# main.net
KiCad netlist of a schematic drawn in EAGLE
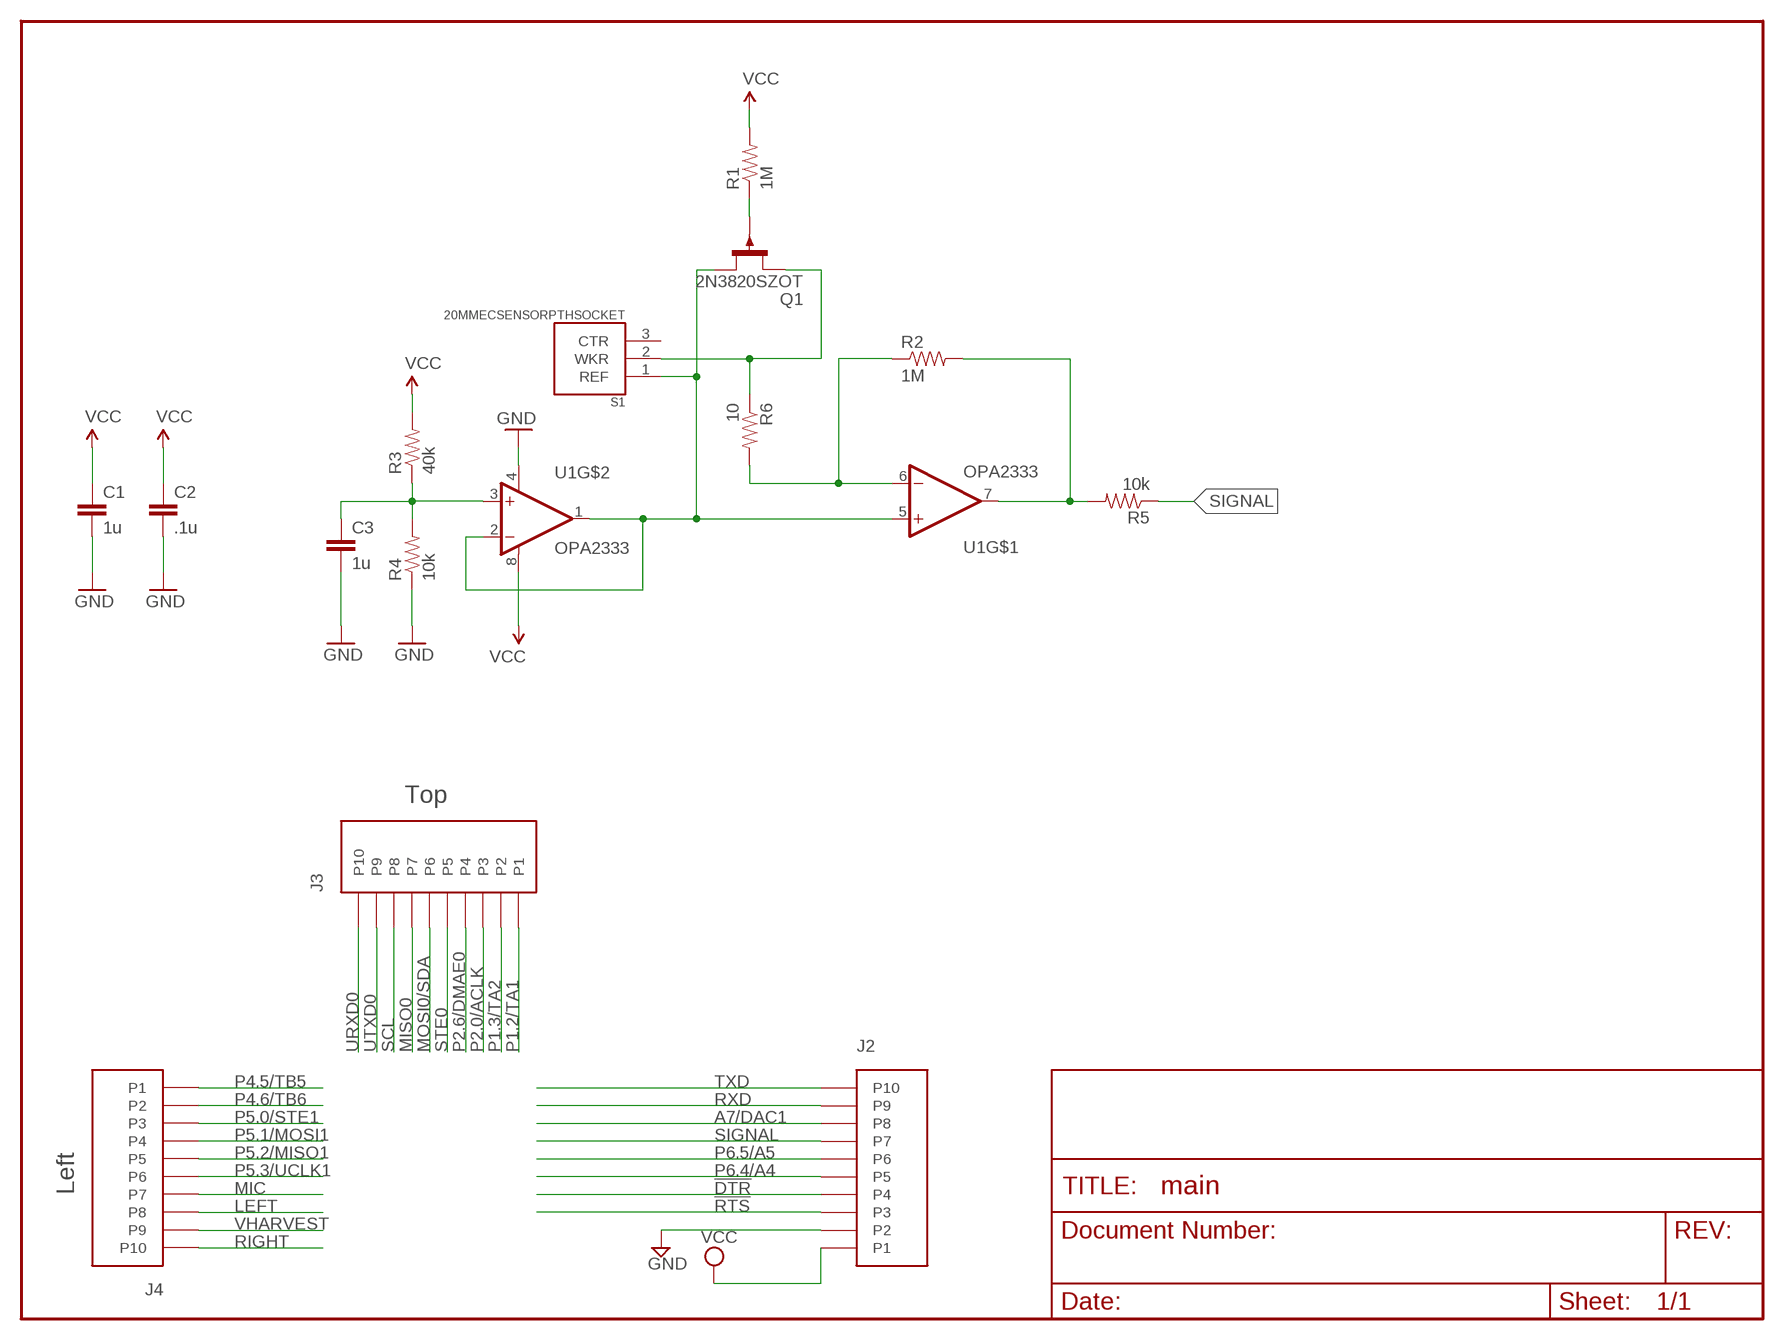
[diagram p0: schematic, sheet 1]

(export (version "E")
  (design (tool "Eeschema 10.0.6"))
  (components
    (comp (ref "C1")
      (value "1u")
      (footprint "eagle-import:0603-CAP")
      (libsource (lib "eagle-import") (part "CAP0603-CAP"))
    )
    (comp (ref "C2")
      (value ".1u")
      (footprint "eagle-import:0603-CAP")
      (libsource (lib "eagle-import") (part "CAP0603-CAP"))
    )
    (comp (ref "C3")
      (value "1u")
      (footprint "eagle-import:0603-CAP")
      (libsource (lib "eagle-import") (part "CAP0603-CAP"))
    )
    (comp (ref "J2")
      (value "HEADER10POS")
      (footprint "eagle-import:10PIN2MMHEADER")
      (libsource (lib "eagle-import") (part "HEADER10POS"))
    )
    (comp (ref "J3")
      (value "HEADER10POS")
      (footprint "eagle-import:10PIN2MMHEADER")
      (libsource (lib "eagle-import") (part "HEADER10POS"))
    )
    (comp (ref "J4")
      (value "HEADER10POS")
      (footprint "eagle-import:10PIN2MMHEADER")
      (libsource (lib "eagle-import") (part "HEADER10POS"))
    )
    (comp (ref "Q1")
      (value "2N3820SZOT")
      (footprint "eagle-import:SOT23-3")
      (libsource (lib "eagle-import") (part "2N3820SZOT"))
    )
    (comp (ref "R1")
      (value "1M")
      (footprint "eagle-import:0603-RES")
      (libsource (lib "eagle-import") (part "RESISTOR0603-RES"))
    )
    (comp (ref "R2")
      (value "1M")
      (footprint "eagle-import:0603-RES")
      (libsource (lib "eagle-import") (part "RESISTOR0603-RES"))
    )
    (comp (ref "R3")
      (value "40k")
      (footprint "eagle-import:0603-RES")
      (libsource (lib "eagle-import") (part "RESISTOR0603-RES"))
    )
    (comp (ref "R4")
      (value "10k")
      (footprint "eagle-import:0603-RES")
      (libsource (lib "eagle-import") (part "RESISTOR0603-RES"))
    )
    (comp (ref "R5")
      (value "10k")
      (footprint "eagle-import:0603-RES")
      (libsource (lib "eagle-import") (part "RESISTOR0603-RES"))
    )
    (comp (ref "R6")
      (value "10")
      (footprint "eagle-import:0603-RES")
      (libsource (lib "eagle-import") (part "RESISTOR0603-RES"))
    )
    (comp (ref "S1")
      (value "20MMECSENSORPTHSOCKET")
      (footprint "eagle-import:20MMSENSOR")
      (libsource (lib "eagle-import") (part "20MMECSENSORPTHSOCKET"))
    )
    (comp (ref "U1")
      (value "OPA2333")
      (footprint "eagle-import:SOIC")
      (libsource (lib "eagle-import") (part "OPA2333"))
    )
  )
  (nets
    (net (code "1") (name "/A7{slash}DAC1") (class "Default")
      (node (ref "J2") (pin "P8") (pinfunction "P8_P8") (pintype "bidirectional"))
    )
    (net (code "2") (name "/LEFT") (class "Default")
      (node (ref "J4") (pin "P8") (pinfunction "P8_P8") (pintype "bidirectional"))
    )
    (net (code "3") (name "/MIC") (class "Default")
      (node (ref "J4") (pin "P7") (pinfunction "P7_P7") (pintype "bidirectional"))
    )
    (net (code "4") (name "/MISO0") (class "Default")
      (node (ref "J3") (pin "P7") (pinfunction "P7_P7") (pintype "bidirectional"))
    )
    (net (code "5") (name "/MOSI0{slash}SDA") (class "Default")
      (node (ref "J3") (pin "P6") (pinfunction "P6_P6") (pintype "bidirectional"))
    )
    (net (code "6") (name "/P1.2{slash}TA1") (class "Default")
      (node (ref "J3") (pin "P1") (pinfunction "P1_P1") (pintype "bidirectional"))
    )
    (net (code "7") (name "/P1.3{slash}TA2") (class "Default")
      (node (ref "J3") (pin "P2") (pinfunction "P2_P2") (pintype "bidirectional"))
    )
    (net (code "8") (name "/P2.0{slash}ACLK") (class "Default")
      (node (ref "J3") (pin "P3") (pinfunction "P3_P3") (pintype "bidirectional"))
    )
    (net (code "9") (name "/P2.6{slash}DMAE0") (class "Default")
      (node (ref "J3") (pin "P4") (pinfunction "P4_P4") (pintype "bidirectional"))
    )
    (net (code "10") (name "/P4.5{slash}TB5") (class "Default")
      (node (ref "J4") (pin "P1") (pinfunction "P1_P1") (pintype "bidirectional"))
    )
    (net (code "11") (name "/P4.6{slash}TB6") (class "Default")
      (node (ref "J4") (pin "P2") (pinfunction "P2_P2") (pintype "bidirectional"))
    )
    (net (code "12") (name "/P5.0{slash}STE1") (class "Default")
      (node (ref "J4") (pin "P3") (pinfunction "P3_P3") (pintype "bidirectional"))
    )
    (net (code "13") (name "/P5.1{slash}MOSI1") (class "Default")
      (node (ref "J4") (pin "P4") (pinfunction "P4_P4") (pintype "bidirectional"))
    )
    (net (code "14") (name "/P5.2{slash}MISO1") (class "Default")
      (node (ref "J4") (pin "P5") (pinfunction "P5_P5") (pintype "bidirectional"))
    )
    (net (code "15") (name "/P5.3{slash}UCLK1") (class "Default")
      (node (ref "J4") (pin "P6") (pinfunction "P6_P6") (pintype "bidirectional"))
    )
    (net (code "16") (name "/P6.4{slash}A4") (class "Default")
      (node (ref "J2") (pin "P5") (pinfunction "P5_P5") (pintype "bidirectional"))
    )
    (net (code "17") (name "/P6.5{slash}A5") (class "Default")
      (node (ref "J2") (pin "P6") (pinfunction "P6_P6") (pintype "bidirectional"))
    )
    (net (code "18") (name "/RIGHT") (class "Default")
      (node (ref "J4") (pin "P10") (pinfunction "P10_P10") (pintype "bidirectional"))
    )
    (net (code "19") (name "/RXD") (class "Default")
      (node (ref "J2") (pin "P9") (pinfunction "P9_P9") (pintype "bidirectional"))
    )
    (net (code "20") (name "/SCL") (class "Default")
      (node (ref "J3") (pin "P8") (pinfunction "P8_P8") (pintype "bidirectional"))
    )
    (net (code "21") (name "/STE0") (class "Default")
      (node (ref "J3") (pin "P5") (pinfunction "P5_P5") (pintype "bidirectional"))
    )
    (net (code "22") (name "/TXD") (class "Default")
      (node (ref "J2") (pin "P10") (pinfunction "P10_P10") (pintype "bidirectional"))
    )
    (net (code "23") (name "/URXD0") (class "Default")
      (node (ref "J3") (pin "P10") (pinfunction "P10_P10") (pintype "bidirectional"))
    )
    (net (code "24") (name "/UTXD0") (class "Default")
      (node (ref "J3") (pin "P9") (pinfunction "P9_P9") (pintype "bidirectional"))
    )
    (net (code "25") (name "/VHARVEST") (class "Default")
      (node (ref "J4") (pin "P9") (pinfunction "P9_P9") (pintype "bidirectional"))
    )
    (net (code "26") (name "/~{DTR}") (class "Default")
      (node (ref "J2") (pin "P4") (pinfunction "P4_P4") (pintype "bidirectional"))
    )
    (net (code "27") (name "/~{RTS}") (class "Default")
      (node (ref "J2") (pin "P3") (pinfunction "P3_P3") (pintype "bidirectional"))
    )
    (net (code "28") (name "GND") (class "Default")
      (node (ref "C1") (pin "2") (pinfunction "2_2") (pintype "passive"))
      (node (ref "C2") (pin "2") (pinfunction "2_2") (pintype "passive"))
      (node (ref "C3") (pin "2") (pinfunction "2_2") (pintype "passive"))
      (node (ref "J2") (pin "P2") (pinfunction "P2_P2") (pintype "bidirectional"))
      (node (ref "R4") (pin "1") (pinfunction "1_1") (pintype "passive"))
      (node (ref "U1") (pin "4") (pinfunction "V-_4") (pintype "power_in"))
    )
    (net (code "29") (name "Net-(Q1-D)") (class "Default")
      (node (ref "Q1") (pin "1") (pinfunction "D_1") (pintype "passive"))
      (node (ref "R6") (pin "1") (pinfunction "1_1") (pintype "passive"))
      (node (ref "S1") (pin "2") (pinfunction "WKR_2") (pintype "bidirectional"))
    )
    (net (code "30") (name "Net-(Q1-G)") (class "Default")
      (node (ref "Q1") (pin "3") (pinfunction "G_3") (pintype "passive"))
      (node (ref "R1") (pin "1") (pinfunction "1_1") (pintype "passive"))
    )
    (net (code "31") (name "Net-(Q1-S)") (class "Default")
      (node (ref "Q1") (pin "2") (pinfunction "S_2") (pintype "passive"))
      (node (ref "S1") (pin "1") (pinfunction "REF_1") (pintype "bidirectional"))
      (node (ref "U1") (pin "1") (pinfunction "OUT_1") (pintype "output"))
      (node (ref "U1") (pin "2") (pinfunction "-IN_2") (pintype "input"))
      (node (ref "U1") (pin "5") (pinfunction "+IN_5") (pintype "input"))
    )
    (net (code "32") (name "Net-(U1A--IN)") (class "Default")
      (node (ref "R2") (pin "1") (pinfunction "1_1") (pintype "passive"))
      (node (ref "R6") (pin "2") (pinfunction "2_2") (pintype "passive"))
      (node (ref "U1") (pin "6") (pinfunction "-IN_6") (pintype "input"))
    )
    (net (code "33") (name "Net-(U1A-OUT)") (class "Default")
      (node (ref "R2") (pin "2") (pinfunction "2_2") (pintype "passive"))
      (node (ref "R5") (pin "2") (pinfunction "2_2") (pintype "passive"))
      (node (ref "U1") (pin "7") (pinfunction "OUT_7") (pintype "output"))
    )
    (net (code "34") (name "Net-(U1B-+IN)") (class "Default")
      (node (ref "C3") (pin "1") (pinfunction "1_1") (pintype "passive"))
      (node (ref "R3") (pin "1") (pinfunction "1_1") (pintype "passive"))
      (node (ref "R4") (pin "2") (pinfunction "2_2") (pintype "passive"))
      (node (ref "U1") (pin "3") (pinfunction "+IN_3") (pintype "input"))
    )
    (net (code "35") (name "SIGNAL") (class "Default")
      (node (ref "J2") (pin "P7") (pinfunction "P7_P7") (pintype "bidirectional"))
      (node (ref "R5") (pin "1") (pinfunction "1_1") (pintype "passive"))
    )
    (net (code "36") (name "VCC") (class "Default")
      (node (ref "C1") (pin "1") (pinfunction "1_1") (pintype "passive"))
      (node (ref "C2") (pin "1") (pinfunction "1_1") (pintype "passive"))
      (node (ref "J2") (pin "P1") (pinfunction "P1_P1") (pintype "bidirectional"))
      (node (ref "R1") (pin "2") (pinfunction "2_2") (pintype "passive"))
      (node (ref "R3") (pin "2") (pinfunction "2_2") (pintype "passive"))
      (node (ref "U1") (pin "8") (pinfunction "V+_8") (pintype "power_in"))
    )
    (net (code "37") (name "unconnected-(S1-CTR-Pad3)") (class "Default")
      (node (ref "S1") (pin "3") (pinfunction "CTR_3") (pintype "bidirectional"))
    )
  )
)
